# SCH_MusicTheoryLesson-CI-TT_2024-12-17.net
KiCad netlist of a schematic drawn in EasyEDA
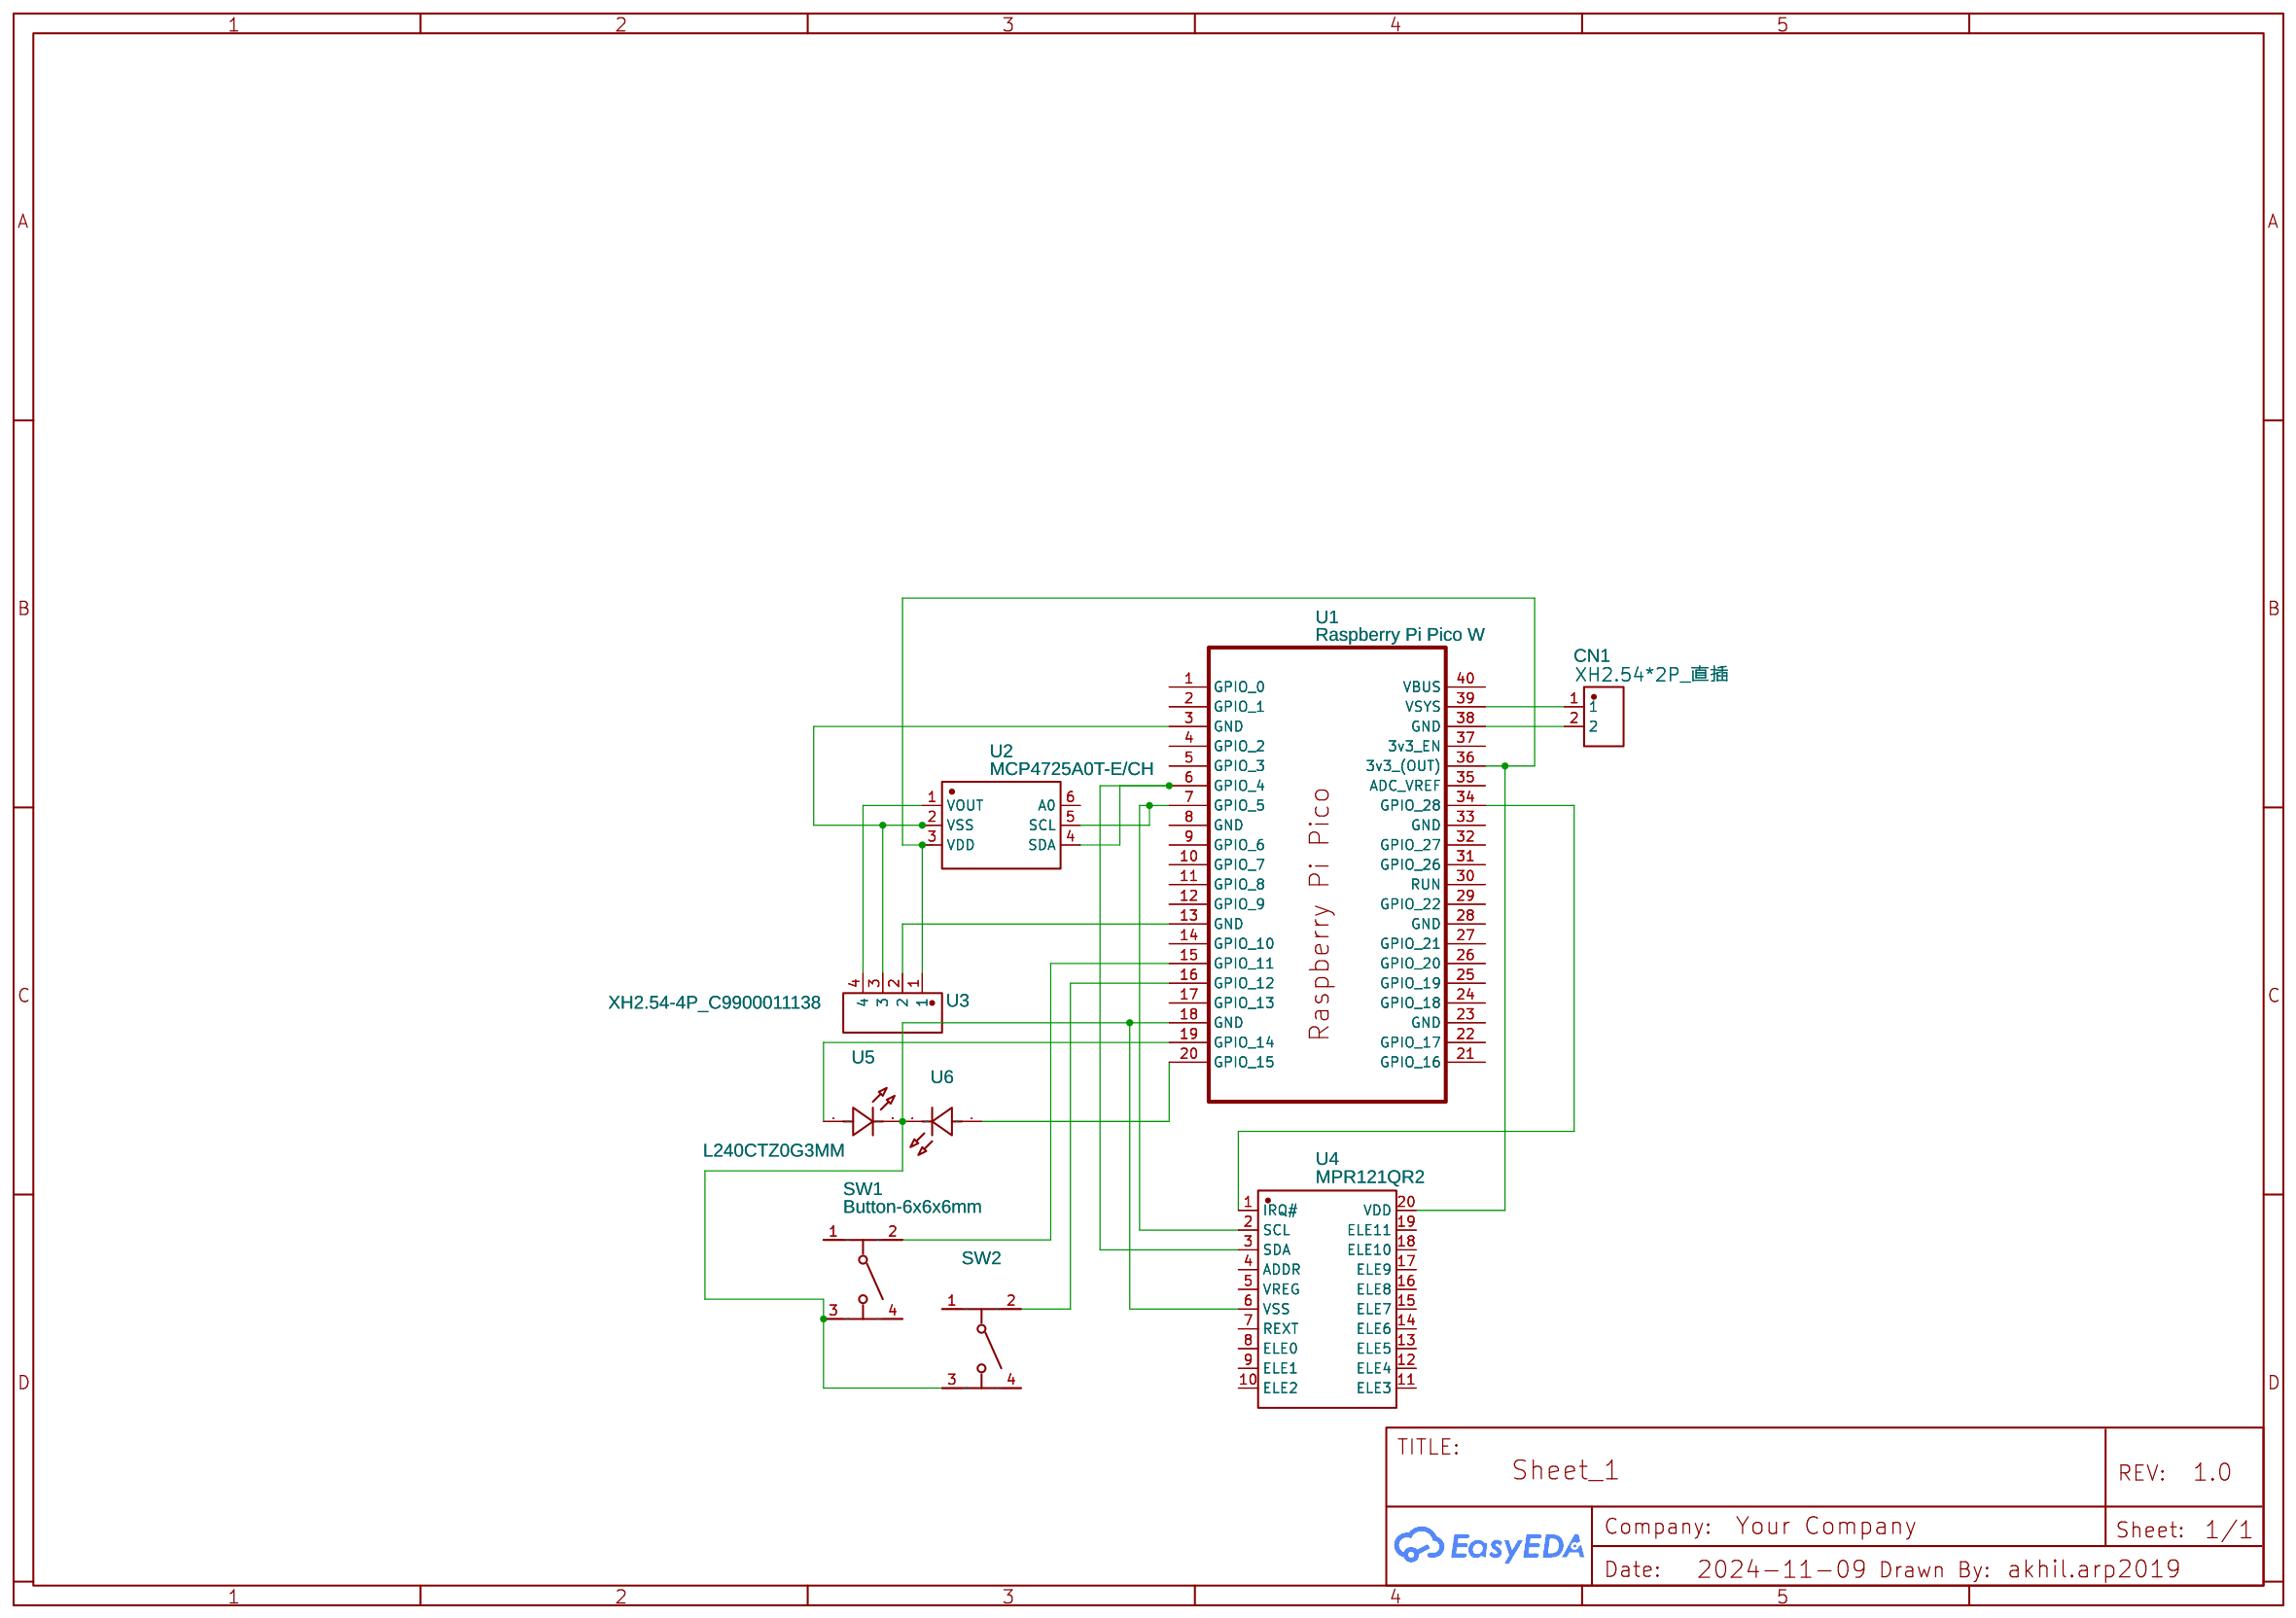
[diagram p0: schematic sheet]

(export (version "E")
  (design (tool "Eeschema 10.0.6"))
  (components
    (comp (ref "CN1") (value "XH2.54*2P_直插") (libsource (lib "") (part "XH2.54*2P_直插")))
    (comp (ref "SW1")
      (value "Button-6x6x6mm")
      (fields
        (field (name "Manufacturer Part") "Switch,6*6*6Plastic head,260G, 0.25mm,Straight line")
        (field (name "Manufacturer") "BBJ")
      )
      (libsource (lib "") (part "Button-6x6x6mm"))
    )
    (comp (ref "SW2")
      (value "Button-6x6x6mm")
      (fields
        (field (name "Manufacturer Part") "Switch,6*6*6Plastic head,260G, 0.25mm,Straight line")
        (field (name "Manufacturer") "BBJ")
      )
      (libsource (lib "") (part "Button-6x6x6mm"))
    )
    (comp (ref "U1") (value "Raspberry Pi Pico W") (libsource (lib "") (part "Raspberry Pi Pico W")))
    (comp (ref "U2")
      (value "MCP4725A0T-E/CH")
      (fields (field (name "Manufacturer") "MICROCHIP(美国微芯)"))
      (libsource (lib "") (part "MCP4725A0T-E/CH"))
    )
    (comp (ref "U3")
      (value "XH2.54-4P_C9900011138")
      (fields (field (name "Manufacturer Part") "XH2.54-4P"))
      (libsource (lib "") (part "XH2.54-4P_C9900011138"))
    )
    (comp (ref "U4")
      (value "MPR121QR2")
      (fields (field (name "Manufacturer") "NXP(恩智浦)"))
      (libsource (lib "") (part "MPR121QR2"))
    )
    (comp (ref "U5") (value "L240CTZ0G3MM") (libsource (lib "") (part "L240CTZ0G3MM_1")))
    (comp (ref "U6") (value "L240CTZ0G3MM") (libsource (lib "") (part "L240CTZ0G3MM")))
  )
  (nets
    (net (code "1") (name "Net-(CN1-Pad2)") (class "Default")
      (node (ref "CN1") (pin "2") (pinfunction "2_2") (pintype "unspecified"))
      (node (ref "U1") (pin "38") (pinfunction "GND_38") (pintype "unspecified"))
    )
    (net (code "2") (name "Net-(U1-3v3_(OUT))") (class "Default")
      (node (ref "U1") (pin "36") (pinfunction "3v3_(OUT)_36") (pintype "unspecified"))
      (node (ref "U2") (pin "3") (pinfunction "VDD_3") (pintype "unspecified"))
      (node (ref "U3") (pin "1") (pinfunction "1_1") (pintype "unspecified"))
      (node (ref "U4") (pin "20") (pinfunction "VDD_20") (pintype "unspecified"))
    )
    (net (code "3") (name "Net-(U1-GND-Pad13)") (class "Default")
      (node (ref "U1") (pin "13") (pinfunction "GND_13") (pintype "unspecified"))
      (node (ref "U3") (pin "2") (pinfunction "2_2") (pintype "unspecified"))
    )
    (net (code "4") (name "Net-(U1-GPIO_4)") (class "Default")
      (node (ref "U1") (pin "6") (pinfunction "GPIO_4_6") (pintype "unspecified"))
      (node (ref "U2") (pin "4") (pinfunction "SDA_4") (pintype "unspecified"))
      (node (ref "U4") (pin "3") (pinfunction "SDA_3") (pintype "unspecified"))
    )
    (net (code "5") (name "Net-(U1-GPIO_5)") (class "Default")
      (node (ref "U1") (pin "7") (pinfunction "GPIO_5_7") (pintype "unspecified"))
      (node (ref "U2") (pin "5") (pinfunction "SCL_5") (pintype "unspecified"))
      (node (ref "U4") (pin "2") (pinfunction "SCL_2") (pintype "unspecified"))
    )
    (net (code "6") (name "Net-(U1-GPIO_11)") (class "Default")
      (node (ref "SW1") (pin "2") (pinfunction "2_2") (pintype "unspecified"))
      (node (ref "U1") (pin "15") (pinfunction "GPIO_11_15") (pintype "unspecified"))
    )
    (net (code "7") (name "Net-(U1-GPIO_12)") (class "Default")
      (node (ref "SW2") (pin "2") (pinfunction "2_2") (pintype "unspecified"))
      (node (ref "U1") (pin "16") (pinfunction "GPIO_12_16") (pintype "unspecified"))
    )
    (net (code "8") (name "Net-(U1-GPIO_14)") (class "Default")
      (node (ref "U1") (pin "19") (pinfunction "GPIO_14_19") (pintype "unspecified"))
      (node (ref "U5") (pin "1") (pinfunction "A_1") (pintype "unspecified"))
    )
    (net (code "9") (name "Net-(U1-GPIO_15)") (class "Default")
      (node (ref "U1") (pin "20") (pinfunction "GPIO_15_20") (pintype "unspecified"))
      (node (ref "U6") (pin "1") (pinfunction "A_1") (pintype "unspecified"))
    )
    (net (code "10") (name "Net-(U1-GPIO_28)") (class "Default")
      (node (ref "U1") (pin "34") (pinfunction "GPIO_28_34") (pintype "unspecified"))
      (node (ref "U4") (pin "1") (pinfunction "IRQ#_1") (pintype "unspecified"))
    )
    (net (code "11") (name "Net-(U1-VSYS)") (class "Default")
      (node (ref "CN1") (pin "1") (pinfunction "1_1") (pintype "unspecified"))
      (node (ref "U1") (pin "39") (pinfunction "VSYS_39") (pintype "unspecified"))
    )
    (net (code "12") (name "Net-(U2-VOUT)") (class "Default")
      (node (ref "U2") (pin "1") (pinfunction "VOUT_1") (pintype "unspecified"))
      (node (ref "U3") (pin "4") (pinfunction "4_4") (pintype "unspecified"))
    )
    (net (code "13") (name "Net-(U2-VSS)") (class "Default")
      (node (ref "U1") (pin "3") (pinfunction "GND_3") (pintype "unspecified"))
      (node (ref "U2") (pin "2") (pinfunction "VSS_2") (pintype "unspecified"))
      (node (ref "U3") (pin "3") (pinfunction "3_3") (pintype "unspecified"))
    )
    (net (code "14") (name "Net-(U4-VSS)") (class "Default")
      (node (ref "SW1") (pin "3") (pinfunction "3_3") (pintype "unspecified"))
      (node (ref "SW2") (pin "3") (pinfunction "3_3") (pintype "unspecified"))
      (node (ref "U1") (pin "18") (pinfunction "GND_18") (pintype "unspecified"))
      (node (ref "U4") (pin "6") (pinfunction "VSS_6") (pintype "unspecified"))
      (node (ref "U5") (pin "2") (pinfunction "K_2") (pintype "unspecified"))
      (node (ref "U6") (pin "2") (pinfunction "K_2") (pintype "unspecified"))
    )
    (net (code "15") (name "unconnected-(SW1-Pad1)") (class "Default")
      (node (ref "SW1") (pin "1") (pinfunction "1_1") (pintype "unspecified"))
    )
    (net (code "16") (name "unconnected-(SW1-Pad4)") (class "Default")
      (node (ref "SW1") (pin "4") (pinfunction "4_4") (pintype "unspecified"))
    )
    (net (code "17") (name "unconnected-(SW2-Pad1)") (class "Default")
      (node (ref "SW2") (pin "1") (pinfunction "1_1") (pintype "unspecified"))
    )
    (net (code "18") (name "unconnected-(SW2-Pad4)") (class "Default")
      (node (ref "SW2") (pin "4") (pinfunction "4_4") (pintype "unspecified"))
    )
    (net (code "19") (name "unconnected-(U1-3v3_EN-Pad37)") (class "Default")
      (node (ref "U1") (pin "37") (pinfunction "3v3_EN_37") (pintype "unspecified"))
    )
    (net (code "20") (name "unconnected-(U1-ADC_VREF-Pad35)") (class "Default")
      (node (ref "U1") (pin "35") (pinfunction "ADC_VREF_35") (pintype "unspecified"))
    )
    (net (code "21") (name "unconnected-(U1-GND-Pad8)") (class "Default")
      (node (ref "U1") (pin "8") (pinfunction "GND_8") (pintype "unspecified"))
    )
    (net (code "22") (name "unconnected-(U1-GND-Pad23)") (class "Default")
      (node (ref "U1") (pin "23") (pinfunction "GND_23") (pintype "unspecified"))
    )
    (net (code "23") (name "unconnected-(U1-GND-Pad28)") (class "Default")
      (node (ref "U1") (pin "28") (pinfunction "GND_28") (pintype "unspecified"))
    )
    (net (code "24") (name "unconnected-(U1-GND-Pad33)") (class "Default")
      (node (ref "U1") (pin "33") (pinfunction "GND_33") (pintype "unspecified"))
    )
    (net (code "25") (name "unconnected-(U1-GPIO_0-Pad1)") (class "Default")
      (node (ref "U1") (pin "1") (pinfunction "GPIO_0_1") (pintype "unspecified"))
    )
    (net (code "26") (name "unconnected-(U1-GPIO_1-Pad2)") (class "Default")
      (node (ref "U1") (pin "2") (pinfunction "GPIO_1_2") (pintype "unspecified"))
    )
    (net (code "27") (name "unconnected-(U1-GPIO_2-Pad4)") (class "Default")
      (node (ref "U1") (pin "4") (pinfunction "GPIO_2_4") (pintype "unspecified"))
    )
    (net (code "28") (name "unconnected-(U1-GPIO_3-Pad5)") (class "Default")
      (node (ref "U1") (pin "5") (pinfunction "GPIO_3_5") (pintype "unspecified"))
    )
    (net (code "29") (name "unconnected-(U1-GPIO_6-Pad9)") (class "Default")
      (node (ref "U1") (pin "9") (pinfunction "GPIO_6_9") (pintype "unspecified"))
    )
    (net (code "30") (name "unconnected-(U1-GPIO_7-Pad10)") (class "Default")
      (node (ref "U1") (pin "10") (pinfunction "GPIO_7_10") (pintype "unspecified"))
    )
    (net (code "31") (name "unconnected-(U1-GPIO_8-Pad11)") (class "Default")
      (node (ref "U1") (pin "11") (pinfunction "GPIO_8_11") (pintype "unspecified"))
    )
    (net (code "32") (name "unconnected-(U1-GPIO_9-Pad12)") (class "Default")
      (node (ref "U1") (pin "12") (pinfunction "GPIO_9_12") (pintype "unspecified"))
    )
    (net (code "33") (name "unconnected-(U1-GPIO_10-Pad14)") (class "Default")
      (node (ref "U1") (pin "14") (pinfunction "GPIO_10_14") (pintype "unspecified"))
    )
    (net (code "34") (name "unconnected-(U1-GPIO_13-Pad17)") (class "Default")
      (node (ref "U1") (pin "17") (pinfunction "GPIO_13_17") (pintype "unspecified"))
    )
    (net (code "35") (name "unconnected-(U1-GPIO_16-Pad21)") (class "Default")
      (node (ref "U1") (pin "21") (pinfunction "GPIO_16_21") (pintype "unspecified"))
    )
    (net (code "36") (name "unconnected-(U1-GPIO_17-Pad22)") (class "Default")
      (node (ref "U1") (pin "22") (pinfunction "GPIO_17_22") (pintype "unspecified"))
    )
    (net (code "37") (name "unconnected-(U1-GPIO_18-Pad24)") (class "Default")
      (node (ref "U1") (pin "24") (pinfunction "GPIO_18_24") (pintype "unspecified"))
    )
    (net (code "38") (name "unconnected-(U1-GPIO_19-Pad25)") (class "Default")
      (node (ref "U1") (pin "25") (pinfunction "GPIO_19_25") (pintype "unspecified"))
    )
    (net (code "39") (name "unconnected-(U1-GPIO_20-Pad26)") (class "Default")
      (node (ref "U1") (pin "26") (pinfunction "GPIO_20_26") (pintype "unspecified"))
    )
    (net (code "40") (name "unconnected-(U1-GPIO_21-Pad27)") (class "Default")
      (node (ref "U1") (pin "27") (pinfunction "GPIO_21_27") (pintype "unspecified"))
    )
    (net (code "41") (name "unconnected-(U1-GPIO_22-Pad29)") (class "Default")
      (node (ref "U1") (pin "29") (pinfunction "GPIO_22_29") (pintype "unspecified"))
    )
    (net (code "42") (name "unconnected-(U1-GPIO_26-Pad31)") (class "Default")
      (node (ref "U1") (pin "31") (pinfunction "GPIO_26_31") (pintype "unspecified"))
    )
    (net (code "43") (name "unconnected-(U1-GPIO_27-Pad32)") (class "Default")
      (node (ref "U1") (pin "32") (pinfunction "GPIO_27_32") (pintype "unspecified"))
    )
    (net (code "44") (name "unconnected-(U1-RUN-Pad30)") (class "Default")
      (node (ref "U1") (pin "30") (pinfunction "RUN_30") (pintype "unspecified"))
    )
    (net (code "45") (name "unconnected-(U1-VBUS-Pad40)") (class "Default")
      (node (ref "U1") (pin "40") (pinfunction "VBUS_40") (pintype "unspecified"))
    )
    (net (code "46") (name "unconnected-(U2-A0-Pad6)") (class "Default")
      (node (ref "U2") (pin "6") (pinfunction "A0_6") (pintype "unspecified"))
    )
    (net (code "47") (name "unconnected-(U4-ADDR-Pad4)") (class "Default")
      (node (ref "U4") (pin "4") (pinfunction "ADDR_4") (pintype "unspecified"))
    )
    (net (code "48") (name "unconnected-(U4-ELE0-Pad8)") (class "Default")
      (node (ref "U4") (pin "8") (pinfunction "ELE0_8") (pintype "unspecified"))
    )
    (net (code "49") (name "unconnected-(U4-ELE1-Pad9)") (class "Default")
      (node (ref "U4") (pin "9") (pinfunction "ELE1_9") (pintype "unspecified"))
    )
    (net (code "50") (name "unconnected-(U4-ELE2-Pad10)") (class "Default")
      (node (ref "U4") (pin "10") (pinfunction "ELE2_10") (pintype "unspecified"))
    )
    (net (code "51") (name "unconnected-(U4-ELE3-Pad11)") (class "Default")
      (node (ref "U4") (pin "11") (pinfunction "ELE3_11") (pintype "unspecified"))
    )
    (net (code "52") (name "unconnected-(U4-ELE4-Pad12)") (class "Default")
      (node (ref "U4") (pin "12") (pinfunction "ELE4_12") (pintype "unspecified"))
    )
    (net (code "53") (name "unconnected-(U4-ELE5-Pad13)") (class "Default")
      (node (ref "U4") (pin "13") (pinfunction "ELE5_13") (pintype "unspecified"))
    )
    (net (code "54") (name "unconnected-(U4-ELE6-Pad14)") (class "Default")
      (node (ref "U4") (pin "14") (pinfunction "ELE6_14") (pintype "unspecified"))
    )
    (net (code "55") (name "unconnected-(U4-ELE7-Pad15)") (class "Default")
      (node (ref "U4") (pin "15") (pinfunction "ELE7_15") (pintype "unspecified"))
    )
    (net (code "56") (name "unconnected-(U4-ELE8-Pad16)") (class "Default")
      (node (ref "U4") (pin "16") (pinfunction "ELE8_16") (pintype "unspecified"))
    )
    (net (code "57") (name "unconnected-(U4-ELE9-Pad17)") (class "Default")
      (node (ref "U4") (pin "17") (pinfunction "ELE9_17") (pintype "unspecified"))
    )
    (net (code "58") (name "unconnected-(U4-ELE10-Pad18)") (class "Default")
      (node (ref "U4") (pin "18") (pinfunction "ELE10_18") (pintype "unspecified"))
    )
    (net (code "59") (name "unconnected-(U4-ELE11-Pad19)") (class "Default")
      (node (ref "U4") (pin "19") (pinfunction "ELE11_19") (pintype "unspecified"))
    )
    (net (code "60") (name "unconnected-(U4-REXT-Pad7)") (class "Default")
      (node (ref "U4") (pin "7") (pinfunction "REXT_7") (pintype "unspecified"))
    )
    (net (code "61") (name "unconnected-(U4-VREG-Pad5)") (class "Default")
      (node (ref "U4") (pin "5") (pinfunction "VREG_5") (pintype "unspecified"))
    )
  )
)
